# Sheet1.net
KiCad netlist of a schematic drawn in Altium Designer
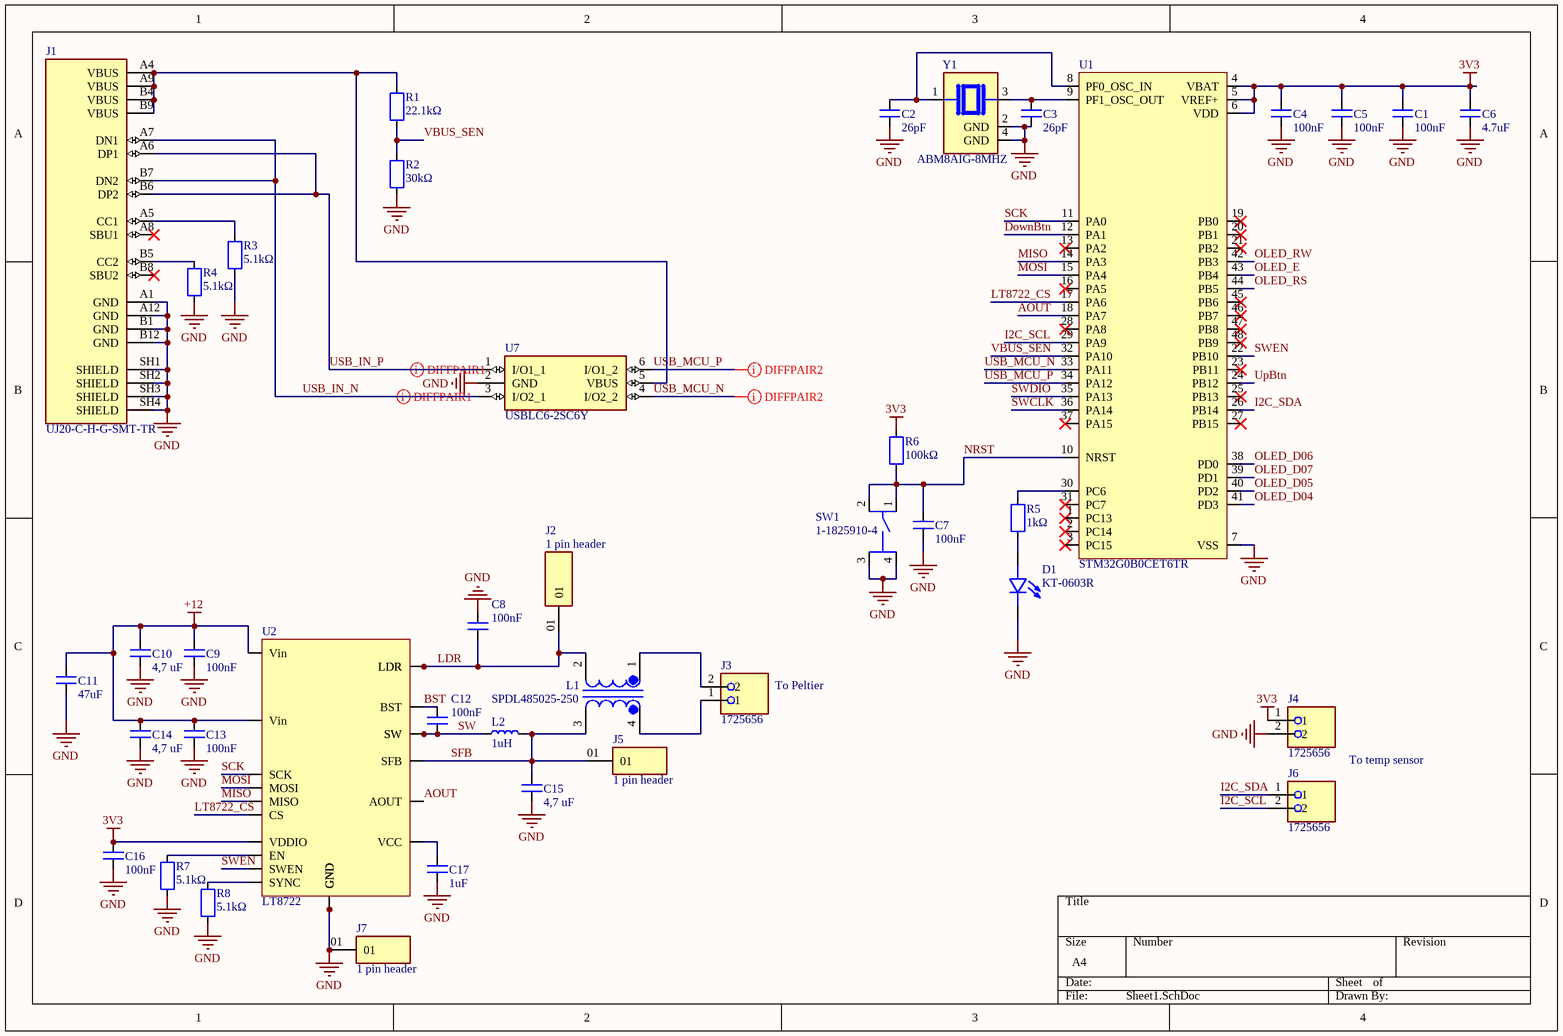
[diagram p0: Sheet1.SchDoc]

(export (version "E")
  (design (tool "Eeschema 10.0.6"))
  (components
    (comp (ref "C1") (value "100nF") (footprint "0603 Imperial") (libsource (lib "Schlib1") (part "0603 C")))
    (comp (ref "C2") (value "26pF") (footprint "0603 Imperial") (libsource (lib "Schlib1") (part "0603 C")))
    (comp (ref "C3") (value "26pF") (footprint "0603 Imperial") (libsource (lib "Schlib1") (part "0603 C")))
    (comp (ref "C4") (value "100nF") (footprint "0603 Imperial") (libsource (lib "Schlib1") (part "0603 C")))
    (comp (ref "C5") (value "100nF") (footprint "0603 Imperial") (libsource (lib "Schlib1") (part "0603 C")))
    (comp (ref "C6") (value "4.7uF") (footprint "0603 Imperial") (libsource (lib "Schlib1") (part "0603 C")))
    (comp (ref "C7") (value "100nF") (footprint "0603 Imperial") (libsource (lib "Schlib1") (part "0603 C")))
    (comp (ref "C8") (value "100nF") (footprint "0603 Imperial") (libsource (lib "Schlib1") (part "0603 C")))
    (comp (ref "C9") (value "100nF") (footprint "0603 Imperial") (libsource (lib "Schlib1") (part "0603 C")))
    (comp (ref "C10")
      (value "4,7 uF")
      (footprint "CAPC3216X180X55LL20T25")
      (libsource (lib "Schlib1") (part "1206 Cap"))
    )
    (comp (ref "C11") (value "47uF") (footprint "FP-TAJD-MFG") (libsource (lib "Schlib1") (part "Large Cap")))
    (comp (ref "C12") (value "100nF") (footprint "0603 Imperial") (libsource (lib "Schlib1") (part "0603 C")))
    (comp (ref "C13") (value "100nF") (footprint "0603 Imperial") (libsource (lib "Schlib1") (part "0603 C")))
    (comp (ref "C14")
      (value "4,7 uF")
      (footprint "CAPC3216X180X55LL20T25")
      (libsource (lib "Schlib1") (part "1206 Cap"))
    )
    (comp (ref "C15")
      (value "4,7 uF")
      (footprint "CAPC3216X180X55LL20T25")
      (libsource (lib "Schlib1") (part "1206 Cap"))
    )
    (comp (ref "C16") (value "100nF") (footprint "0603 Imperial") (libsource (lib "Schlib1") (part "0603 C")))
    (comp (ref "C17") (value "1uF") (footprint "0603 Imperial") (libsource (lib "Schlib1") (part "0603 C")))
    (comp (ref "D1")
      (value "KT-0603R")
      (footprint "LED_KT-0603R")
      (description "Red 0603 Light Emitting Diodes")
      (fields (field (name "MF") "Hubei KENTO Elec"))
      (libsource (lib "Schlib1") (part "KT-0603R"))
    )
    (comp (ref "J1")
      (value "UJ20-C-H-G-SMT-TR")
      (footprint "CUI_UJ20-C-H-G-SMT-TR")
      (fields (field (name "MF") "Same Sky"))
      (libsource (lib "Schlib1") (part "UJ20-C-H-G-SMT-TR"))
    )
    (comp (ref "J2")
      (value "1 pin header")
      (footprint "SAMTEC_MTMM-101-X-X-S-X")
      (description "Connector Header Through Hole 1 position")
      (fields (field (name "MF") "Samtec") (field (name "MP") "MTMM-101-05-G-S-225"))
      (libsource (lib "") (part "1 pin header_1"))
    )
    (comp (ref "J3")
      (value "1725656")
      (footprint "PHOENIX_1725656")
      (description "PCB Terminal Screw 2.54mm 20AWG 160V 6A 2 Position COMBICON MPT Series ¦ Phoenix Contact 1725656")
      (fields (field (name "MF") "Phoenix Contact"))
      (libsource (lib "") (part "1725656_1"))
    )
    (comp (ref "J4")
      (value "1725656")
      (footprint "PHOENIX_1725656")
      (description "PCB Terminal Screw 2.54mm 20AWG 160V 6A 2 Position COMBICON MPT Series ¦ Phoenix Contact 1725656")
      (fields (field (name "MF") "Phoenix Contact"))
      (libsource (lib "Schlib1") (part "1725656"))
    )
    (comp (ref "J5")
      (value "1 pin header")
      (footprint "SAMTEC_MTMM-101-X-X-S-X")
      (description "Connector Header Through Hole 1 position")
      (fields (field (name "MF") "Samtec") (field (name "MP") "MTMM-101-05-G-S-225"))
      (libsource (lib "Schlib1") (part "1 pin header"))
    )
    (comp (ref "J6")
      (value "1725656")
      (footprint "PHOENIX_1725656")
      (description "PCB Terminal Screw 2.54mm 20AWG 160V 6A 2 Position COMBICON MPT Series ¦ Phoenix Contact 1725656")
      (fields (field (name "MF") "Phoenix Contact"))
      (libsource (lib "Schlib1") (part "1725656"))
    )
    (comp (ref "J7")
      (value "1 pin header")
      (footprint "SAMTEC_MTMM-101-X-X-S-X")
      (description "Connector Header Through Hole 1 position")
      (fields (field (name "MF") "Samtec") (field (name "MP") "MTMM-101-05-G-S-225"))
      (libsource (lib "Schlib1") (part "1 pin header"))
    )
    (comp (ref "L1")
      (value "SPDL485025-250")
      (footprint "IND_SPDL485025-250-2P-T")
      (fields (field (name "MP") "SPDL485025-250-2P-T"))
      (libsource (lib "Schlib1") (part "SPDL485025-250-2P-T"))
    )
    (comp (ref "L2")
      (value "1uH")
      (footprint "1uH Power Inductor")
      (libsource (lib "Schlib1") (part "1uH Power Inductor"))
    )
    (comp (ref "R1") (value "22.1kΩ") (footprint "0603 Imperial") (libsource (lib "Schlib1") (part "0603 R")))
    (comp (ref "R2") (value "30kΩ") (footprint "0603 Imperial") (libsource (lib "Schlib1") (part "0603 R")))
    (comp (ref "R3") (value "5.1kΩ") (footprint "0603 Imperial") (libsource (lib "Schlib1") (part "0603 R")))
    (comp (ref "R4") (value "5.1kΩ") (footprint "0603 Imperial") (libsource (lib "Schlib1") (part "0603 R")))
    (comp (ref "R5") (value "1kΩ") (footprint "0603 Imperial") (libsource (lib "Schlib1") (part "0603 R")))
    (comp (ref "R6") (value "100kΩ") (footprint "0603 Imperial") (libsource (lib "Schlib1") (part "0603 R")))
    (comp (ref "R7") (value "5.1kΩ") (footprint "0603 Imperial") (libsource (lib "Schlib1") (part "0603 R")))
    (comp (ref "R8") (value "5.1kΩ") (footprint "0603 Imperial") (libsource (lib "Schlib1") (part "0603 R")))
    (comp (ref "SW1")
      (value "1-1825910-4")
      (footprint "TE_1-1825910-4")
      (description "Switch Tactile OFF _ON_ SPST Round Button PC Pins 0.05A 24VDC 100000Cycles 1.56N Thru-Hole")
      (fields (field (name "MF") "TE Connectivity"))
      (libsource (lib "Schlib1") (part "1-1825910-4"))
    )
    (comp (ref "U1")
      (value "STM32G0B0CET6TR")
      (footprint "STM32G0B0CET6TR")
      (libsource (lib "Schlib1") (part "STM32G0B0CET6TR"))
    )
    (comp (ref "U2") (value "LT8722") (footprint "LT8722") (libsource (lib "Schlib1") (part "LT8722")))
    (comp (ref "U7")
      (value "USBLC6-2SC6Y")
      (footprint "USB ESD protection")
      (description "17V Clamp 5A (8/20µs) Ipp Tvs Diode Surface Mount SOT-23-6")
      (fields (field (name "MF") "STMicroelectronics"))
      (libsource (lib "Schlib1") (part "USB ESD protection"))
    )
    (comp (ref "Y1")
      (value "ABM8AIG-8MHZ")
      (footprint "XTAL_ABM8AIG-8.000MHZ-8-V1R-T")
      (description "8 MHz Â±10ppm Crystal 8pF 500 Ohms 4-SMD, No Lead")
      (fields (field (name "MF") "Abracon LLC") (field (name "MP") "ABM8AIG-8.000MHZ-8-V1R-T"))
      (libsource (lib "Schlib1") (part "ABM8AIG-8.000MHZ-8-V1R-T"))
    )
  )
  (nets
    (net (code "1") (name "+12") (class "Default")
      (node (ref "C10") (pin "1") (pinfunction "1_1") (pintype "passive"))
      (node (ref "C11") (pin "2") (pinfunction "2_2") (pintype "passive"))
      (node (ref "C13") (pin "1") (pinfunction "1_1") (pintype "passive"))
      (node (ref "C14") (pin "1") (pinfunction "1_1") (pintype "passive"))
      (node (ref "C9") (pin "1") (pinfunction "1_1") (pintype "passive"))
      (node (ref "U2") (pin "11") (pinfunction "Vin_11") (pintype "passive"))
      (node (ref "U2") (pin "4") (pinfunction "Vin_4") (pintype "passive"))
    )
    (net (code "3") (name "/AOUT") (class "Default")
      (node (ref "U1") (pin "18") (pinfunction "PA7_18") (pintype "passive"))
      (node (ref "U2") (pin "20") (pinfunction "AOUT_20") (pintype "passive"))
    )
    (net (code "4") (name "/BST") (class "Default")
      (node (ref "C12") (pin "1") (pinfunction "1_1") (pintype "passive"))
      (node (ref "U2") (pin "3") (pinfunction "BST_3") (pintype "passive"))
    )
    (net (code "5") (name "/DownBtn") (class "Default")
      (node (ref "U1") (pin "12") (pinfunction "PA1_12") (pintype "passive"))
    )
    (net (code "6") (name "/I2C_SCL") (class "Default")
      (node (ref "J6") (pin "2") (pinfunction "2_2") (pintype "passive"))
      (node (ref "U1") (pin "29") (pinfunction "PA9_29") (pintype "passive"))
    )
    (net (code "7") (name "/I2C_SDA") (class "Default")
      (node (ref "J6") (pin "1") (pinfunction "1_1") (pintype "passive"))
      (node (ref "U1") (pin "26") (pinfunction "PB14_26") (pintype "passive"))
    )
    (net (code "8") (name "/LDR") (class "Default")
      (node (ref "C8") (pin "2") (pinfunction "2_2") (pintype "passive"))
      (node (ref "J2") (pin "01") (pinfunction "01_01") (pintype "passive"))
      (node (ref "L1") (pin "2") (pinfunction "2_2") (pintype "passive"))
      (node (ref "U2") (pin "8") (pinfunction "LDR_8") (pintype "passive"))
      (node (ref "U2") (pin "9") (pinfunction "LDR_9") (pintype "passive"))
    )
    (net (code "9") (name "/LT8722_CS") (class "Default")
      (node (ref "U1") (pin "17") (pinfunction "PA6_17") (pintype "passive"))
      (node (ref "U2") (pin "15") (pinfunction "CS_15") (pintype "passive"))
    )
    (net (code "10") (name "/MISO") (class "Default")
      (node (ref "U1") (pin "14") (pinfunction "PA3_14") (pintype "passive"))
      (node (ref "U2") (pin "18") (pinfunction "MISO_18") (pintype "passive"))
    )
    (net (code "11") (name "/MOSI") (class "Default")
      (node (ref "U1") (pin "15") (pinfunction "PA4_15") (pintype "passive"))
      (node (ref "U2") (pin "17") (pinfunction "MOSI_17") (pintype "passive"))
    )
    (net (code "12") (name "/NRST") (class "Default")
      (node (ref "C7") (pin "1") (pinfunction "1_1") (pintype "passive"))
      (node (ref "R6") (pin "1") (pinfunction "1_1") (pintype "passive"))
      (node (ref "SW1") (pin "1") (pinfunction "1_1") (pintype "passive"))
      (node (ref "SW1") (pin "2") (pinfunction "2_2") (pintype "passive"))
      (node (ref "U1") (pin "10") (pinfunction "NRST_10") (pintype "passive"))
    )
    (net (code "13") (name "/OLED_D04") (class "Default")
      (node (ref "U1") (pin "41") (pinfunction "PD3_41") (pintype "passive"))
    )
    (net (code "14") (name "/OLED_D05") (class "Default")
      (node (ref "U1") (pin "40") (pinfunction "PD2_40") (pintype "passive"))
    )
    (net (code "15") (name "/OLED_D06") (class "Default")
      (node (ref "U1") (pin "38") (pinfunction "PD0_38") (pintype "passive"))
    )
    (net (code "16") (name "/OLED_D07") (class "Default")
      (node (ref "U1") (pin "39") (pinfunction "PD1_39") (pintype "passive"))
    )
    (net (code "17") (name "/OLED_E") (class "Default")
      (node (ref "U1") (pin "43") (pinfunction "PB4_43") (pintype "passive"))
    )
    (net (code "18") (name "/OLED_RS") (class "Default")
      (node (ref "U1") (pin "44") (pinfunction "PB5_44") (pintype "passive"))
    )
    (net (code "19") (name "/OLED_RW") (class "Default")
      (node (ref "U1") (pin "42") (pinfunction "PB3_42") (pintype "passive"))
    )
    (net (code "20") (name "/SCK") (class "Default")
      (node (ref "U1") (pin "11") (pinfunction "PA0_11") (pintype "passive"))
      (node (ref "U2") (pin "16") (pinfunction "SCK_16") (pintype "passive"))
    )
    (net (code "21") (name "/SFB") (class "Default")
      (node (ref "C15") (pin "1") (pinfunction "1_1") (pintype "passive"))
      (node (ref "J5") (pin "01") (pinfunction "01_01") (pintype "passive"))
      (node (ref "L1") (pin "3") (pinfunction "3_3") (pintype "passive"))
      (node (ref "L2") (pin "2") (pinfunction "2_2") (pintype "passive"))
      (node (ref "U2") (pin "12") (pinfunction "SFB_12") (pintype "passive"))
    )
    (net (code "22") (name "/SW") (class "Default")
      (node (ref "C12") (pin "2") (pinfunction "2_2") (pintype "passive"))
      (node (ref "L2") (pin "1") (pinfunction "1_1") (pintype "passive"))
      (node (ref "U2") (pin "6") (pinfunction "SW_6") (pintype "passive"))
      (node (ref "U2") (pin "7") (pinfunction "SW_7") (pintype "passive"))
    )
    (net (code "23") (name "/SWCLK") (class "Default")
      (node (ref "U1") (pin "36") (pinfunction "PA14_36") (pintype "passive"))
    )
    (net (code "24") (name "/SWDIO") (class "Default")
      (node (ref "U1") (pin "35") (pinfunction "PA13_35") (pintype "passive"))
    )
    (net (code "25") (name "/SWEN") (class "Default")
      (node (ref "U1") (pin "22") (pinfunction "PB10_22") (pintype "passive"))
      (node (ref "U2") (pin "13") (pinfunction "SWEN_13") (pintype "passive"))
    )
    (net (code "26") (name "/USB_IN_N") (class "Default")
      (node (ref "J1") (pin "A7") (pinfunction "DN1_A7") (pintype "bidirectional"))
      (node (ref "J1") (pin "B7") (pinfunction "DN2_B7") (pintype "bidirectional"))
      (node (ref "U7") (pin "3") (pinfunction "I/O2_1_3") (pintype "bidirectional"))
    )
    (net (code "27") (name "/USB_IN_P") (class "Default")
      (node (ref "J1") (pin "A6") (pinfunction "DP1_A6") (pintype "bidirectional"))
      (node (ref "J1") (pin "B6") (pinfunction "DP2_B6") (pintype "bidirectional"))
      (node (ref "U7") (pin "1") (pinfunction "I/O1_1_1") (pintype "bidirectional"))
    )
    (net (code "28") (name "/USB_MCU_N") (class "Default")
      (node (ref "U1") (pin "33") (pinfunction "PA11_33") (pintype "passive"))
      (node (ref "U7") (pin "4") (pinfunction "I/O2_2_4") (pintype "bidirectional"))
    )
    (net (code "29") (name "/USB_MCU_P") (class "Default")
      (node (ref "U1") (pin "34") (pinfunction "PA12_34") (pintype "passive"))
      (node (ref "U7") (pin "6") (pinfunction "I/O1_2_6") (pintype "bidirectional"))
    )
    (net (code "30") (name "/UpBtn") (class "Default")
      (node (ref "U1") (pin "24") (pinfunction "PB12_24") (pintype "passive"))
    )
    (net (code "31") (name "/VBUS_SEN") (class "Default")
      (node (ref "R1") (pin "1") (pinfunction "1_1") (pintype "passive"))
      (node (ref "R2") (pin "2") (pinfunction "2_2") (pintype "passive"))
      (node (ref "U1") (pin "32") (pinfunction "PA10_32") (pintype "passive"))
    )
    (net (code "32") (name "3V3") (class "Default")
      (node (ref "C1") (pin "1") (pinfunction "1_1") (pintype "passive"))
      (node (ref "C16") (pin "1") (pinfunction "1_1") (pintype "passive"))
      (node (ref "C4") (pin "1") (pinfunction "1_1") (pintype "passive"))
      (node (ref "C5") (pin "1") (pinfunction "1_1") (pintype "passive"))
      (node (ref "C6") (pin "1") (pinfunction "1_1") (pintype "passive"))
      (node (ref "J4") (pin "1") (pinfunction "1_1") (pintype "passive"))
      (node (ref "R6") (pin "2") (pinfunction "2_2") (pintype "passive"))
      (node (ref "U1") (pin "4") (pinfunction "VBAT_4") (pintype "passive"))
      (node (ref "U1") (pin "5") (pinfunction "VREF+_5") (pintype "passive"))
      (node (ref "U1") (pin "6") (pinfunction "VDD_6") (pintype "passive"))
      (node (ref "U2") (pin "14") (pinfunction "VDDIO_14") (pintype "passive"))
    )
    (net (code "33") (name "GND") (class "Default")
      (node (ref "C1") (pin "2") (pinfunction "2_2") (pintype "passive"))
      (node (ref "C10") (pin "2") (pinfunction "2_2") (pintype "passive"))
      (node (ref "C11") (pin "1") (pinfunction "1_1") (pintype "passive"))
      (node (ref "C13") (pin "2") (pinfunction "2_2") (pintype "passive"))
      (node (ref "C14") (pin "2") (pinfunction "2_2") (pintype "passive"))
      (node (ref "C15") (pin "2") (pinfunction "2_2") (pintype "passive"))
      (node (ref "C16") (pin "2") (pinfunction "2_2") (pintype "passive"))
      (node (ref "C17") (pin "2") (pinfunction "2_2") (pintype "passive"))
      (node (ref "C2") (pin "2") (pinfunction "2_2") (pintype "passive"))
      (node (ref "C3") (pin "2") (pinfunction "2_2") (pintype "passive"))
      (node (ref "C4") (pin "2") (pinfunction "2_2") (pintype "passive"))
      (node (ref "C5") (pin "2") (pinfunction "2_2") (pintype "passive"))
      (node (ref "C6") (pin "2") (pinfunction "2_2") (pintype "passive"))
      (node (ref "C7") (pin "2") (pinfunction "2_2") (pintype "passive"))
      (node (ref "C8") (pin "1") (pinfunction "1_1") (pintype "passive"))
      (node (ref "C9") (pin "2") (pinfunction "2_2") (pintype "passive"))
      (node (ref "D1") (pin "C") (pinfunction "C_C") (pintype "passive"))
      (node (ref "J1") (pin "A1") (pinfunction "GND_A1") (pintype "power_in"))
      (node (ref "J1") (pin "A12") (pinfunction "GND_A12") (pintype "power_in"))
      (node (ref "J1") (pin "B1") (pinfunction "GND_B1") (pintype "power_in"))
      (node (ref "J1") (pin "B12") (pinfunction "GND_B12") (pintype "power_in"))
      (node (ref "J1") (pin "SH1") (pinfunction "SHIELD_SH1") (pintype "passive"))
      (node (ref "J1") (pin "SH2") (pinfunction "SHIELD_SH2") (pintype "passive"))
      (node (ref "J1") (pin "SH3") (pinfunction "SHIELD_SH3") (pintype "passive"))
      (node (ref "J1") (pin "SH4") (pinfunction "SHIELD_SH4") (pintype "passive"))
      (node (ref "J4") (pin "2") (pinfunction "2_2") (pintype "passive"))
      (node (ref "J7") (pin "01") (pinfunction "01_01") (pintype "passive"))
      (node (ref "R2") (pin "1") (pinfunction "1_1") (pintype "passive"))
      (node (ref "R3") (pin "1") (pinfunction "1_1") (pintype "passive"))
      (node (ref "R4") (pin "1") (pinfunction "1_1") (pintype "passive"))
      (node (ref "R7") (pin "1") (pinfunction "1_1") (pintype "passive"))
      (node (ref "R8") (pin "1") (pinfunction "1_1") (pintype "passive"))
      (node (ref "SW1") (pin "3") (pinfunction "3_3") (pintype "passive"))
      (node (ref "SW1") (pin "4") (pinfunction "4_4") (pintype "passive"))
      (node (ref "U1") (pin "7") (pinfunction "VSS_7") (pintype "passive"))
      (node (ref "U2") (pin "10") (pinfunction "GND_10") (pintype "passive"))
      (node (ref "U2") (pin "21") (pinfunction "GND_21") (pintype "passive"))
      (node (ref "U2") (pin "22") (pinfunction "GND_22") (pintype "passive"))
      (node (ref "U2") (pin "5") (pinfunction "GND_5") (pintype "passive"))
      (node (ref "U7") (pin "2") (pinfunction "GND_2") (pintype "passive"))
      (node (ref "Y1") (pin "2") (pinfunction "GND_2") (pintype "power_in"))
      (node (ref "Y1") (pin "4") (pinfunction "GND_4") (pintype "power_in"))
    )
    (net (code "34") (name "Net-(D1-PadA)") (class "Default")
      (node (ref "D1") (pin "A") (pinfunction "A_A") (pintype "passive"))
      (node (ref "R5") (pin "1") (pinfunction "1_1") (pintype "passive"))
    )
    (net (code "35") (name "Net-(J1-CC1)") (class "Default")
      (node (ref "J1") (pin "A5") (pinfunction "CC1_A5") (pintype "bidirectional"))
      (node (ref "R3") (pin "2") (pinfunction "2_2") (pintype "passive"))
    )
    (net (code "36") (name "Net-(J1-CC2)") (class "Default")
      (node (ref "J1") (pin "B5") (pinfunction "CC2_B5") (pintype "bidirectional"))
      (node (ref "R4") (pin "2") (pinfunction "2_2") (pintype "passive"))
    )
    (net (code "37") (name "Net-(J3-Pad1)") (class "Default")
      (node (ref "J3") (pin "1") (pinfunction "1_1") (pintype "passive"))
      (node (ref "L1") (pin "4") (pinfunction "4_4") (pintype "passive"))
    )
    (net (code "38") (name "Net-(J3-Pad2)") (class "Default")
      (node (ref "J3") (pin "2") (pinfunction "2_2") (pintype "passive"))
      (node (ref "L1") (pin "1") (pinfunction "1_1") (pintype "passive"))
    )
    (net (code "39") (name "Net-(U1-PC6)") (class "Default")
      (node (ref "R5") (pin "2") (pinfunction "2_2") (pintype "passive"))
      (node (ref "U1") (pin "30") (pinfunction "PC6_30") (pintype "passive"))
    )
    (net (code "40") (name "Net-(U1-PF0_OSC_IN)") (class "Default")
      (node (ref "C2") (pin "1") (pinfunction "1_1") (pintype "passive"))
      (node (ref "U1") (pin "8") (pinfunction "PF0_OSC_IN_8") (pintype "passive"))
      (node (ref "Y1") (pin "1") (pinfunction "1_1") (pintype "passive"))
    )
    (net (code "41") (name "Net-(U1-PF1_OSC_OUT)") (class "Default")
      (node (ref "C3") (pin "1") (pinfunction "1_1") (pintype "passive"))
      (node (ref "U1") (pin "9") (pinfunction "PF1_OSC_OUT_9") (pintype "passive"))
      (node (ref "Y1") (pin "3") (pinfunction "2_3") (pintype "passive"))
    )
    (net (code "42") (name "Net-(U2-EN)") (class "Default")
      (node (ref "R7") (pin "2") (pinfunction "2_2") (pintype "passive"))
      (node (ref "U2") (pin "19") (pinfunction "EN_19") (pintype "passive"))
    )
    (net (code "43") (name "Net-(U2-SYNC)") (class "Default")
      (node (ref "R8") (pin "2") (pinfunction "2_2") (pintype "passive"))
      (node (ref "U2") (pin "1") (pinfunction "SYNC_1") (pintype "passive"))
    )
    (net (code "44") (name "Net-(U2-VCC)") (class "Default")
      (node (ref "C17") (pin "1") (pinfunction "1_1") (pintype "passive"))
      (node (ref "U2") (pin "2") (pinfunction "VCC_2") (pintype "passive"))
    )
    (net (code "45") (name "Net-(U7-VBUS)") (class "Default")
      (node (ref "J1") (pin "A4") (pinfunction "VBUS_A4") (pintype "power_in"))
      (node (ref "J1") (pin "A9") (pinfunction "VBUS_A9") (pintype "power_in"))
      (node (ref "J1") (pin "B4") (pinfunction "VBUS_B4") (pintype "power_in"))
      (node (ref "J1") (pin "B9") (pinfunction "VBUS_B9") (pintype "power_in"))
      (node (ref "R1") (pin "2") (pinfunction "2_2") (pintype "passive"))
      (node (ref "U7") (pin "5") (pinfunction "VBUS_5") (pintype "bidirectional"))
    )
    (net (code "46") (name "unconnected-(J1-SBU1-PadA8)") (class "Default")
      (node (ref "J1") (pin "A8") (pinfunction "SBU1_A8") (pintype "bidirectional+no_connect"))
    )
    (net (code "47") (name "unconnected-(J1-SBU2-PadB8)") (class "Default")
      (node (ref "J1") (pin "B8") (pinfunction "SBU2_B8") (pintype "bidirectional+no_connect"))
    )
    (net (code "48") (name "unconnected-(U1-PA2-Pad13)") (class "Default")
      (node (ref "U1") (pin "13") (pinfunction "PA2_13") (pintype "passive+no_connect"))
    )
    (net (code "49") (name "unconnected-(U1-PA5-Pad16)") (class "Default")
      (node (ref "U1") (pin "16") (pinfunction "PA5_16") (pintype "passive+no_connect"))
    )
    (net (code "50") (name "unconnected-(U1-PA8-Pad28)") (class "Default")
      (node (ref "U1") (pin "28") (pinfunction "PA8_28") (pintype "passive+no_connect"))
    )
    (net (code "51") (name "unconnected-(U1-PA15-Pad37)") (class "Default")
      (node (ref "U1") (pin "37") (pinfunction "PA15_37") (pintype "passive+no_connect"))
    )
    (net (code "52") (name "unconnected-(U1-PB0-Pad19)") (class "Default")
      (node (ref "U1") (pin "19") (pinfunction "PB0_19") (pintype "passive+no_connect"))
    )
    (net (code "53") (name "unconnected-(U1-PB1-Pad20)") (class "Default")
      (node (ref "U1") (pin "20") (pinfunction "PB1_20") (pintype "passive+no_connect"))
    )
    (net (code "54") (name "unconnected-(U1-PB2-Pad21)") (class "Default")
      (node (ref "U1") (pin "21") (pinfunction "PB2_21") (pintype "passive+no_connect"))
    )
    (net (code "55") (name "unconnected-(U1-PB6-Pad45)") (class "Default")
      (node (ref "U1") (pin "45") (pinfunction "PB6_45") (pintype "passive+no_connect"))
    )
    (net (code "56") (name "unconnected-(U1-PB7-Pad46)") (class "Default")
      (node (ref "U1") (pin "46") (pinfunction "PB7_46") (pintype "passive+no_connect"))
    )
    (net (code "57") (name "unconnected-(U1-PB8-Pad47)") (class "Default")
      (node (ref "U1") (pin "47") (pinfunction "PB8_47") (pintype "passive+no_connect"))
    )
    (net (code "58") (name "unconnected-(U1-PB9-Pad48)") (class "Default")
      (node (ref "U1") (pin "48") (pinfunction "PB9_48") (pintype "passive+no_connect"))
    )
    (net (code "59") (name "unconnected-(U1-PB11-Pad23)") (class "Default")
      (node (ref "U1") (pin "23") (pinfunction "PB11_23") (pintype "passive+no_connect"))
    )
    (net (code "60") (name "unconnected-(U1-PB13-Pad25)") (class "Default")
      (node (ref "U1") (pin "25") (pinfunction "PB13_25") (pintype "passive+no_connect"))
    )
    (net (code "61") (name "unconnected-(U1-PB15-Pad27)") (class "Default")
      (node (ref "U1") (pin "27") (pinfunction "PB15_27") (pintype "passive+no_connect"))
    )
    (net (code "62") (name "unconnected-(U1-PC7-Pad31)") (class "Default")
      (node (ref "U1") (pin "31") (pinfunction "PC7_31") (pintype "passive+no_connect"))
    )
    (net (code "63") (name "unconnected-(U1-PC13-Pad1)") (class "Default")
      (node (ref "U1") (pin "1") (pinfunction "PC13_1") (pintype "passive+no_connect"))
    )
    (net (code "64") (name "unconnected-(U1-PC14-Pad2)") (class "Default")
      (node (ref "U1") (pin "2") (pinfunction "PC14_2") (pintype "passive+no_connect"))
    )
    (net (code "65") (name "unconnected-(U1-PC15-Pad3)") (class "Default")
      (node (ref "U1") (pin "3") (pinfunction "PC15_3") (pintype "passive+no_connect"))
    )
  )
)
